# DATALOGGER_BP_V1.net
KiCad netlist of a schematic drawn in EAGLE
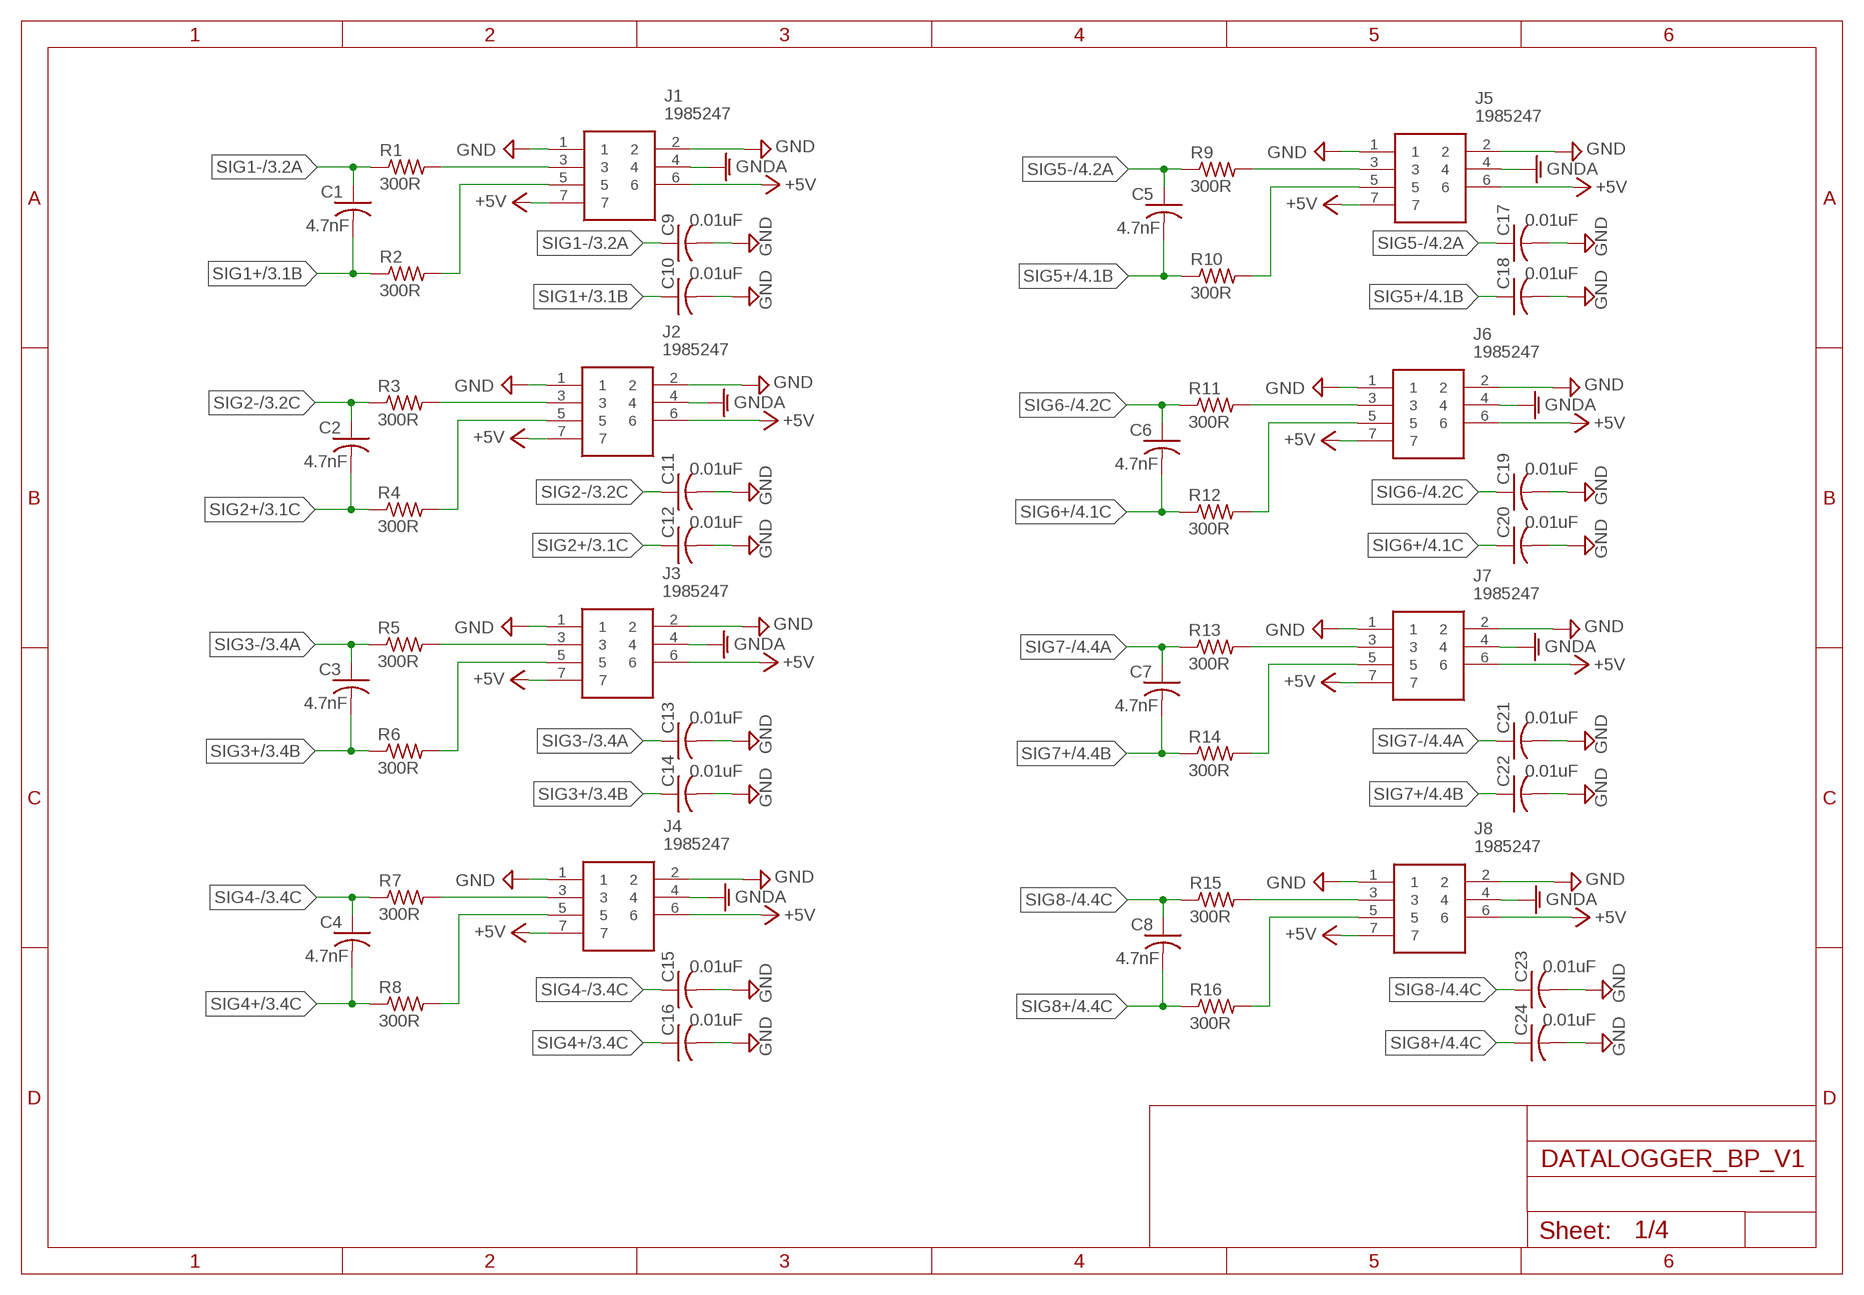
[diagram p0: schematic, sheet 1]
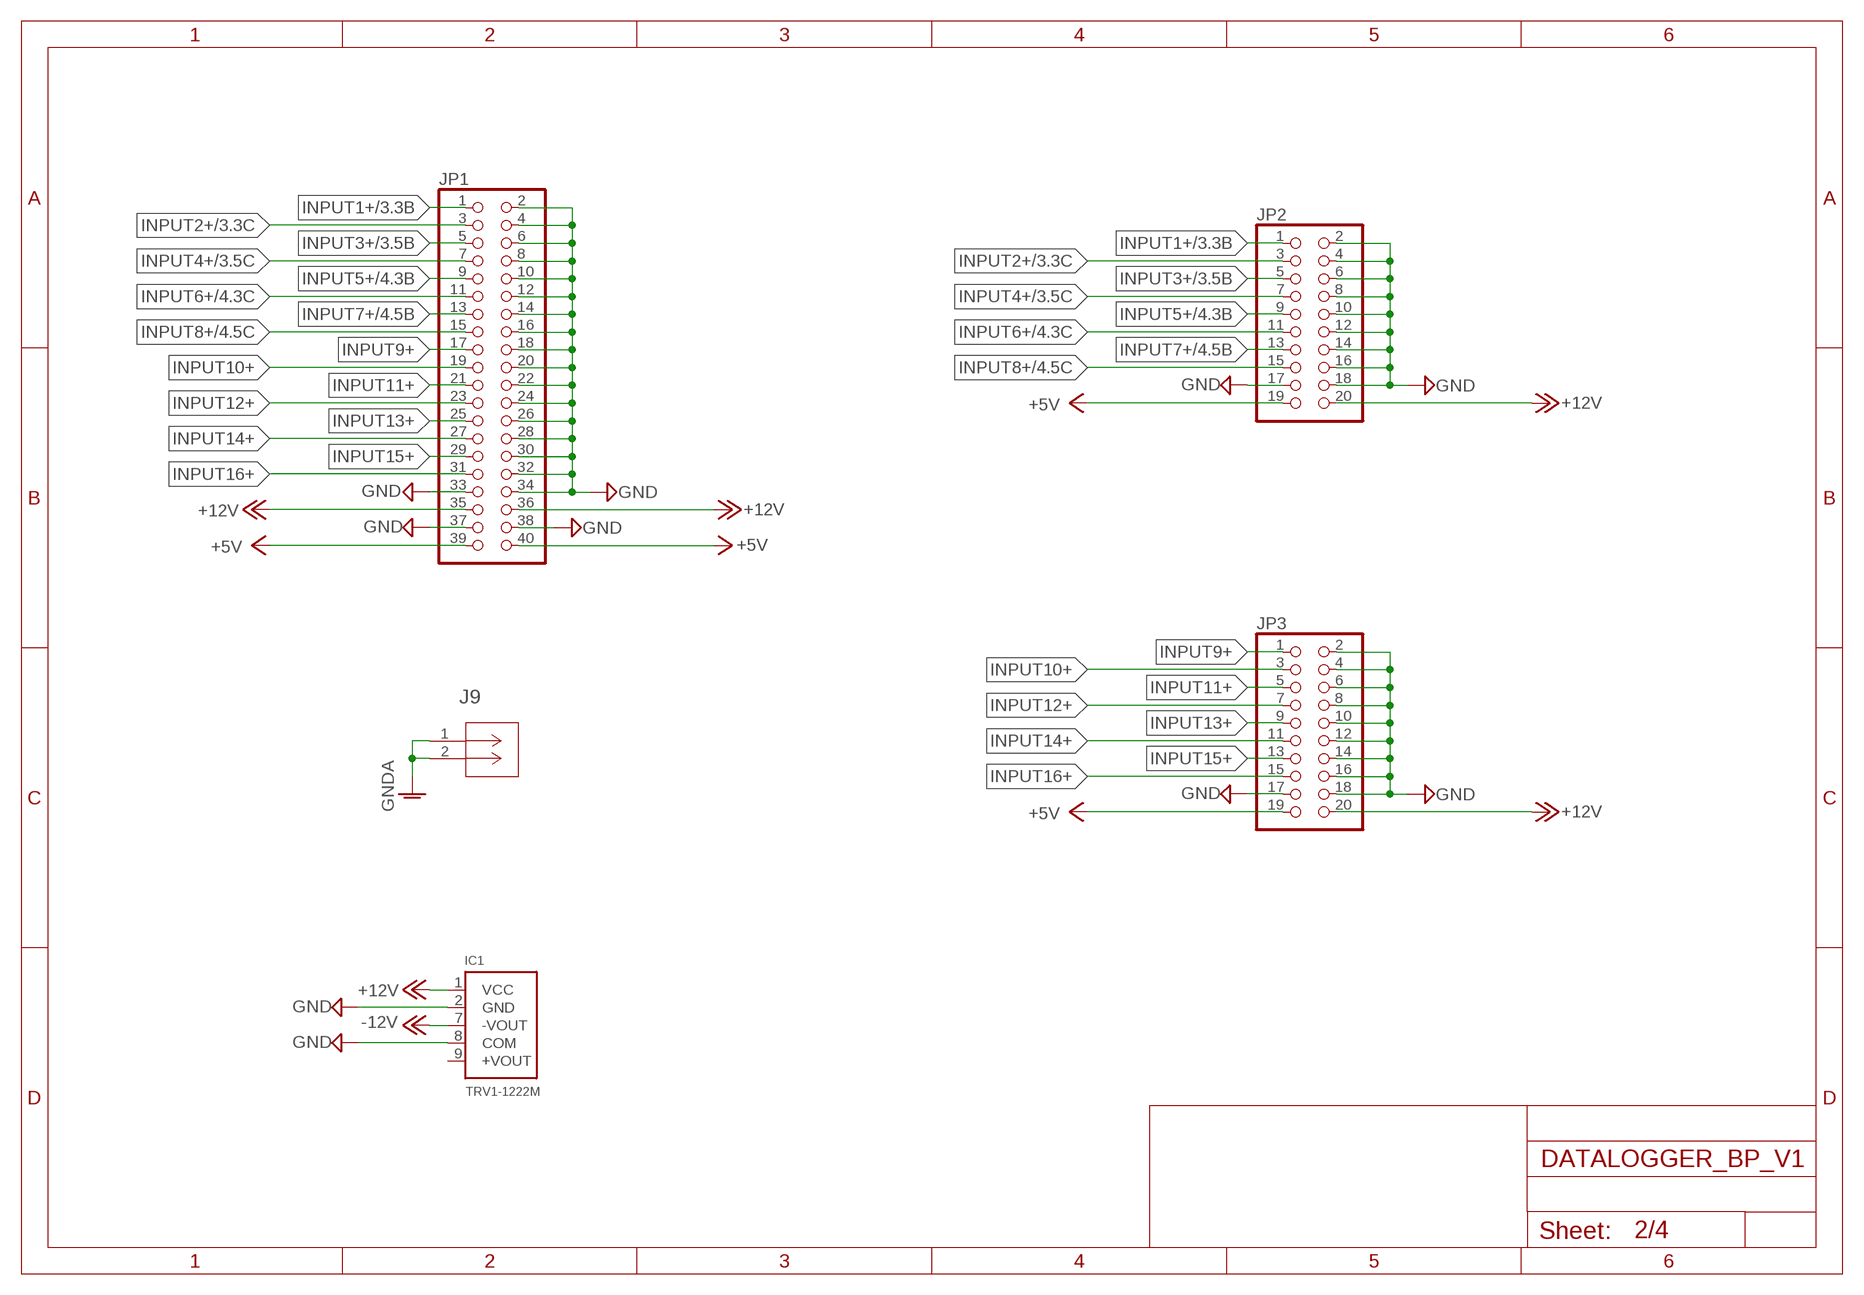
[diagram p1: schematic, sheet 2]
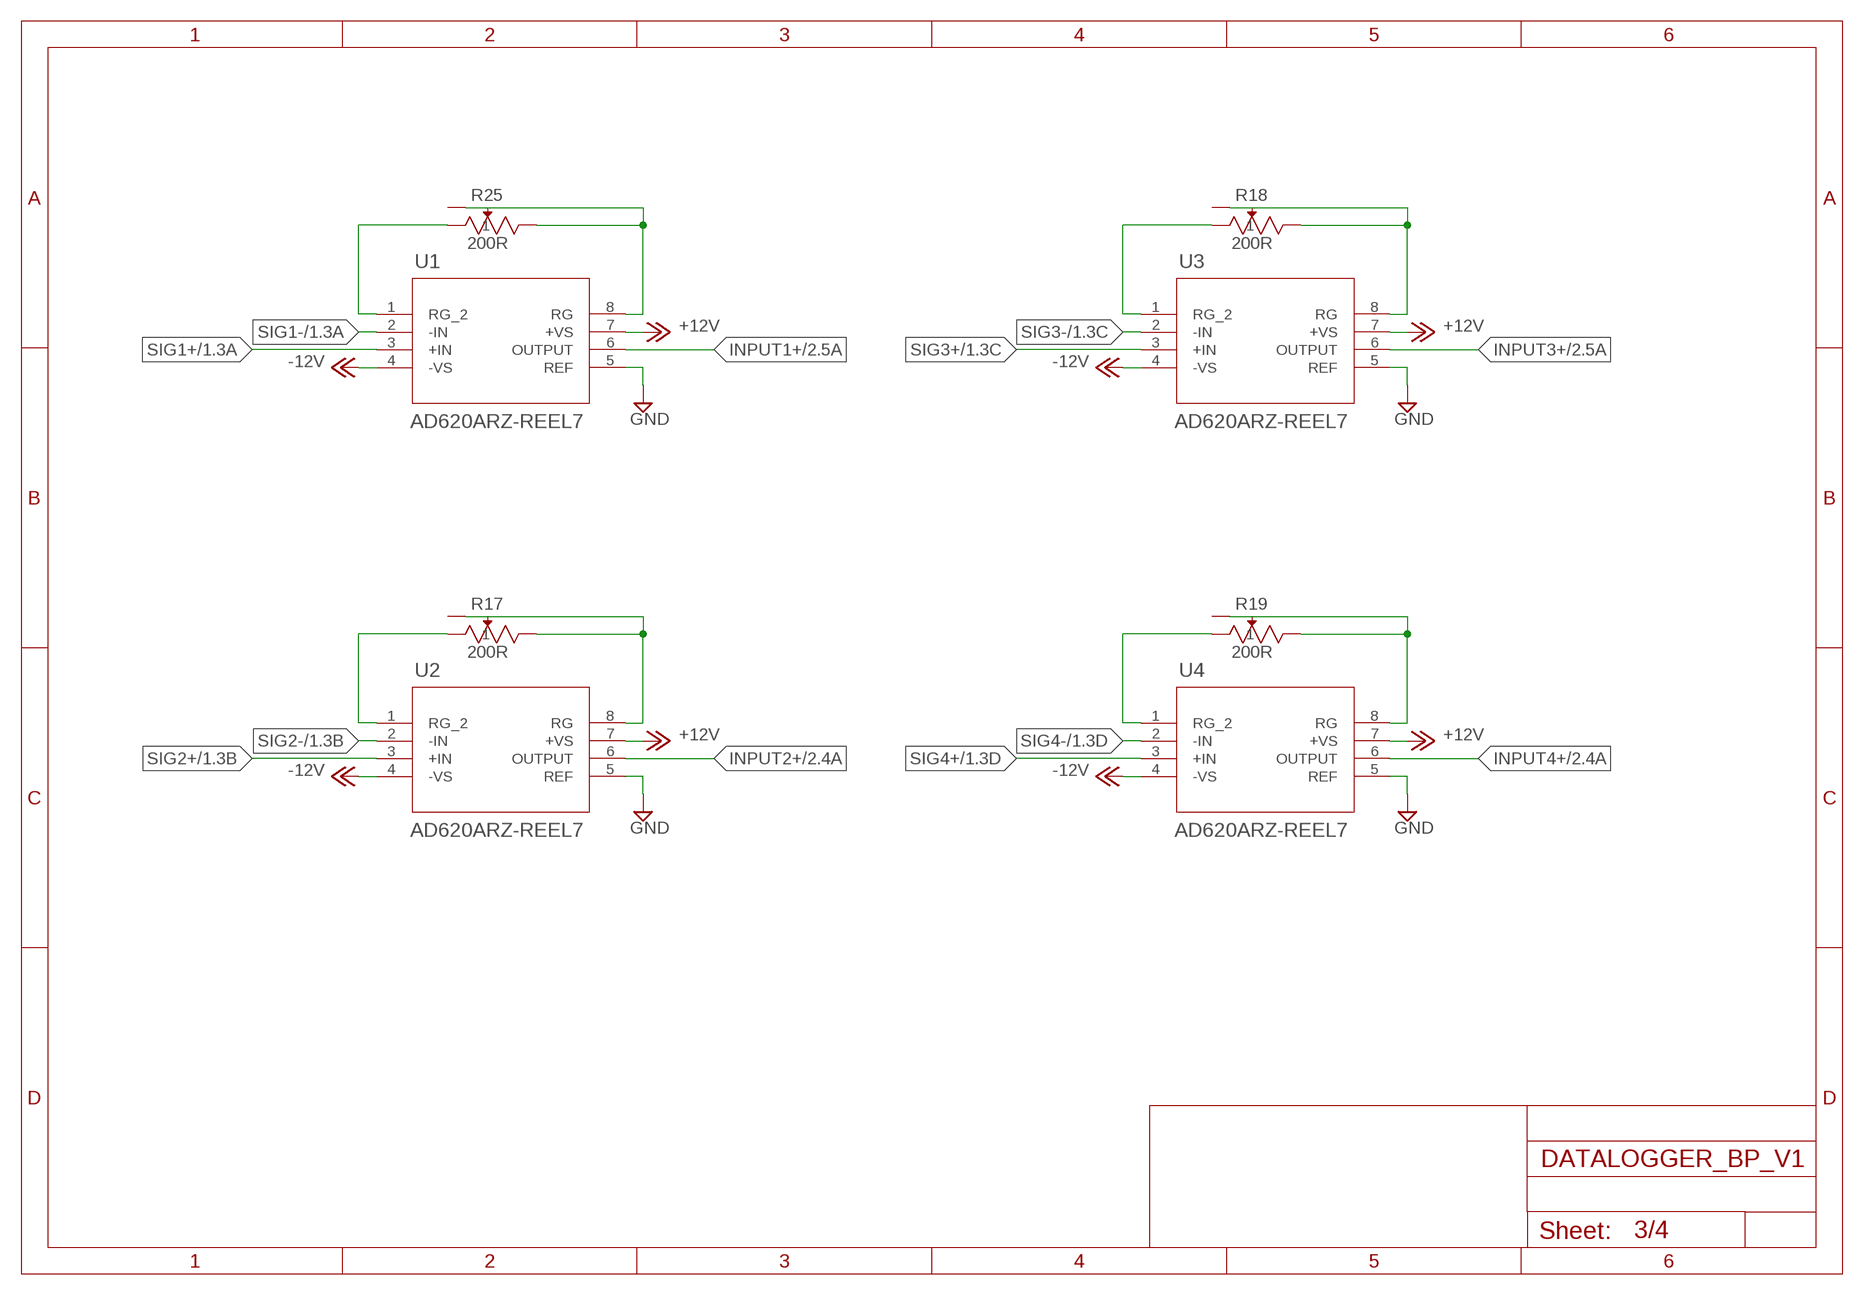
[diagram p2: schematic, sheet 3]
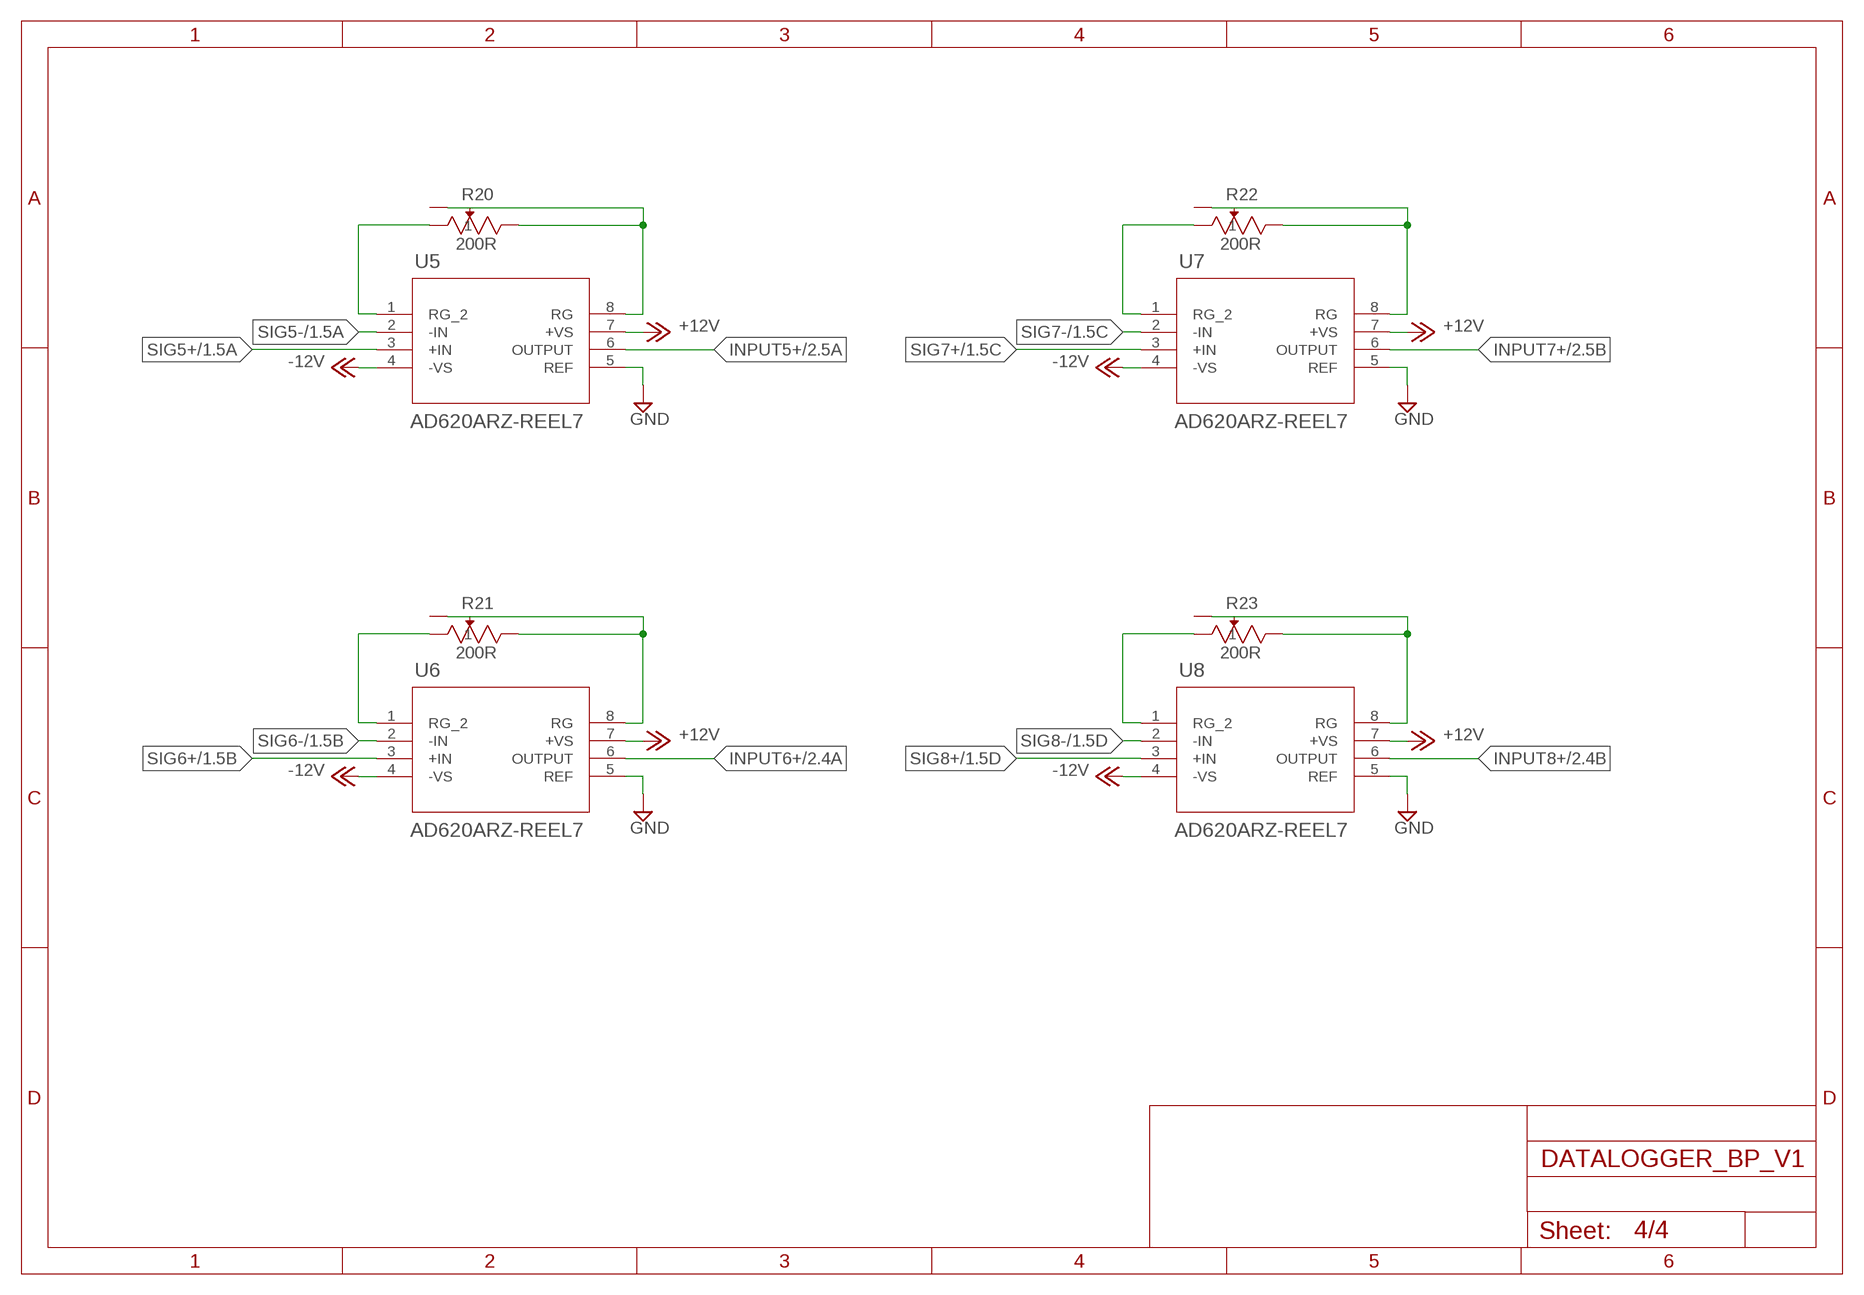
[diagram p3: schematic, sheet 4]

(export (version "E")
  (design (tool "Eeschema 10.0.6"))
  (components
    (comp (ref "R20")
      (value "200R")
      (footprint "eagle-import:RES3_22A_TTE")
      (fields (field (name "MANUFACTURER_PART_NUMBER") "22AR200LFTR"))
      (libsource (lib "eagle-import") (part "22AR200LFTR"))
    )
    (comp (ref "R21")
      (value "200R")
      (footprint "eagle-import:RES3_22A_TTE")
      (fields (field (name "MANUFACTURER_PART_NUMBER") "22AR200LFTR"))
      (libsource (lib "eagle-import") (part "22AR200LFTR"))
    )
    (comp (ref "R22")
      (value "200R")
      (footprint "eagle-import:RES3_22A_TTE")
      (fields (field (name "MANUFACTURER_PART_NUMBER") "22AR200LFTR"))
      (libsource (lib "eagle-import") (part "22AR200LFTR"))
    )
    (comp (ref "R23")
      (value "200R")
      (footprint "eagle-import:RES3_22A_TTE")
      (fields (field (name "MANUFACTURER_PART_NUMBER") "22AR200LFTR"))
      (libsource (lib "eagle-import") (part "22AR200LFTR"))
    )
    (comp (ref "U5")
      (value "AD620ARZ-REEL7")
      (footprint "eagle-import:R_8_ADI")
      (libsource (lib "eagle-import") (part "AD620ARZ-REEL7"))
    )
    (comp (ref "U6")
      (value "AD620ARZ-REEL7")
      (footprint "eagle-import:R_8_ADI")
      (libsource (lib "eagle-import") (part "AD620ARZ-REEL7"))
    )
    (comp (ref "U7")
      (value "AD620ARZ-REEL7")
      (footprint "eagle-import:R_8_ADI")
      (libsource (lib "eagle-import") (part "AD620ARZ-REEL7"))
    )
    (comp (ref "U8")
      (value "AD620ARZ-REEL7")
      (footprint "eagle-import:R_8_ADI")
      (libsource (lib "eagle-import") (part "AD620ARZ-REEL7"))
    )
    (comp (ref "R17")
      (value "200R")
      (footprint "eagle-import:RES3_22A_TTE")
      (fields (field (name "MANUFACTURER_PART_NUMBER") "22AR200LFTR"))
      (libsource (lib "eagle-import") (part "22AR200LFTR"))
    )
    (comp (ref "R18")
      (value "200R")
      (footprint "eagle-import:RES3_22A_TTE")
      (fields (field (name "MANUFACTURER_PART_NUMBER") "22AR200LFTR"))
      (libsource (lib "eagle-import") (part "22AR200LFTR"))
    )
    (comp (ref "R19")
      (value "200R")
      (footprint "eagle-import:RES3_22A_TTE")
      (fields (field (name "MANUFACTURER_PART_NUMBER") "22AR200LFTR"))
      (libsource (lib "eagle-import") (part "22AR200LFTR"))
    )
    (comp (ref "R25")
      (value "200R")
      (footprint "eagle-import:RES3_22A_TTE")
      (fields (field (name "MANUFACTURER_PART_NUMBER") "22AR200LFTR"))
      (libsource (lib "eagle-import") (part "22AR200LFTR"))
    )
    (comp (ref "U1")
      (value "AD620ARZ-REEL7")
      (footprint "eagle-import:R_8_ADI")
      (libsource (lib "eagle-import") (part "AD620ARZ-REEL7"))
    )
    (comp (ref "U2")
      (value "AD620ARZ-REEL7")
      (footprint "eagle-import:R_8_ADI")
      (libsource (lib "eagle-import") (part "AD620ARZ-REEL7"))
    )
    (comp (ref "U3")
      (value "AD620ARZ-REEL7")
      (footprint "eagle-import:R_8_ADI")
      (libsource (lib "eagle-import") (part "AD620ARZ-REEL7"))
    )
    (comp (ref "U4")
      (value "AD620ARZ-REEL7")
      (footprint "eagle-import:R_8_ADI")
      (libsource (lib "eagle-import") (part "AD620ARZ-REEL7"))
    )
    (comp (ref "C1")
      (value "4.7nF")
      (footprint "eagle-import:C0805")
      (libsource (lib "eagle-import") (part "C-USC0805"))
    )
    (comp (ref "C2")
      (value "4.7nF")
      (footprint "eagle-import:C0805")
      (libsource (lib "eagle-import") (part "C-USC0805"))
    )
    (comp (ref "C3")
      (value "4.7nF")
      (footprint "eagle-import:C0805")
      (libsource (lib "eagle-import") (part "C-USC0805"))
    )
    (comp (ref "C4")
      (value "4.7nF")
      (footprint "eagle-import:C0805")
      (libsource (lib "eagle-import") (part "C-USC0805"))
    )
    (comp (ref "C5")
      (value "4.7nF")
      (footprint "eagle-import:C0805")
      (libsource (lib "eagle-import") (part "C-USC0805"))
    )
    (comp (ref "C6")
      (value "4.7nF")
      (footprint "eagle-import:C0805")
      (libsource (lib "eagle-import") (part "C-USC0805"))
    )
    (comp (ref "C7")
      (value "4.7nF")
      (footprint "eagle-import:C0805")
      (libsource (lib "eagle-import") (part "C-USC0805"))
    )
    (comp (ref "C8")
      (value "4.7nF")
      (footprint "eagle-import:C0805")
      (libsource (lib "eagle-import") (part "C-USC0805"))
    )
    (comp (ref "C9")
      (value "0.01uF")
      (footprint "eagle-import:C0805")
      (libsource (lib "eagle-import") (part "C-USC0805"))
    )
    (comp (ref "C10")
      (value "0.01uF")
      (footprint "eagle-import:C0805")
      (libsource (lib "eagle-import") (part "C-USC0805"))
    )
    (comp (ref "C11")
      (value "0.01uF")
      (footprint "eagle-import:C0805")
      (libsource (lib "eagle-import") (part "C-USC0805"))
    )
    (comp (ref "C12")
      (value "0.01uF")
      (footprint "eagle-import:C0805")
      (libsource (lib "eagle-import") (part "C-USC0805"))
    )
    (comp (ref "C13")
      (value "0.01uF")
      (footprint "eagle-import:C0805")
      (libsource (lib "eagle-import") (part "C-USC0805"))
    )
    (comp (ref "C14")
      (value "0.01uF")
      (footprint "eagle-import:C0805")
      (libsource (lib "eagle-import") (part "C-USC0805"))
    )
    (comp (ref "C15")
      (value "0.01uF")
      (footprint "eagle-import:C0805")
      (libsource (lib "eagle-import") (part "C-USC0805"))
    )
    (comp (ref "C16")
      (value "0.01uF")
      (footprint "eagle-import:C0805")
      (libsource (lib "eagle-import") (part "C-USC0805"))
    )
    (comp (ref "C17")
      (value "0.01uF")
      (footprint "eagle-import:C0805")
      (libsource (lib "eagle-import") (part "C-USC0805"))
    )
    (comp (ref "C18")
      (value "0.01uF")
      (footprint "eagle-import:C0805")
      (libsource (lib "eagle-import") (part "C-USC0805"))
    )
    (comp (ref "C19")
      (value "0.01uF")
      (footprint "eagle-import:C0805")
      (libsource (lib "eagle-import") (part "C-USC0805"))
    )
    (comp (ref "C20")
      (value "0.01uF")
      (footprint "eagle-import:C0805")
      (libsource (lib "eagle-import") (part "C-USC0805"))
    )
    (comp (ref "C21")
      (value "0.01uF")
      (footprint "eagle-import:C0805")
      (libsource (lib "eagle-import") (part "C-USC0805"))
    )
    (comp (ref "C22")
      (value "0.01uF")
      (footprint "eagle-import:C0805")
      (libsource (lib "eagle-import") (part "C-USC0805"))
    )
    (comp (ref "C23")
      (value "0.01uF")
      (footprint "eagle-import:C0805")
      (libsource (lib "eagle-import") (part "C-USC0805"))
    )
    (comp (ref "C24")
      (value "0.01uF")
      (footprint "eagle-import:C0805")
      (libsource (lib "eagle-import") (part "C-USC0805"))
    )
    (comp (ref "J1")
      (value "1985247")
      (footprint "eagle-import:1985247")
      (fields (field (name "MOUSER_PART_NUMBER") "651-1985247"))
      (libsource (lib "eagle-import") (part "1985247"))
    )
    (comp (ref "J2")
      (value "1985247")
      (footprint "eagle-import:1985247")
      (fields (field (name "MOUSER_PART_NUMBER") "651-1985247"))
      (libsource (lib "eagle-import") (part "1985247"))
    )
    (comp (ref "J3")
      (value "1985247")
      (footprint "eagle-import:1985247")
      (fields (field (name "MOUSER_PART_NUMBER") "651-1985247"))
      (libsource (lib "eagle-import") (part "1985247"))
    )
    (comp (ref "J4")
      (value "1985247")
      (footprint "eagle-import:1985247")
      (fields (field (name "MOUSER_PART_NUMBER") "651-1985247"))
      (libsource (lib "eagle-import") (part "1985247"))
    )
    (comp (ref "J5")
      (value "1985247")
      (footprint "eagle-import:1985247")
      (fields (field (name "MOUSER_PART_NUMBER") "651-1985247"))
      (libsource (lib "eagle-import") (part "1985247"))
    )
    (comp (ref "J6")
      (value "1985247")
      (footprint "eagle-import:1985247")
      (fields (field (name "MOUSER_PART_NUMBER") "651-1985247"))
      (libsource (lib "eagle-import") (part "1985247"))
    )
    (comp (ref "J7")
      (value "1985247")
      (footprint "eagle-import:1985247")
      (fields (field (name "MOUSER_PART_NUMBER") "651-1985247"))
      (libsource (lib "eagle-import") (part "1985247"))
    )
    (comp (ref "J8")
      (value "1985247")
      (footprint "eagle-import:1985247")
      (fields (field (name "MOUSER_PART_NUMBER") "651-1985247"))
      (libsource (lib "eagle-import") (part "1985247"))
    )
    (comp (ref "R1")
      (value "300R")
      (footprint "eagle-import:R0805")
      (libsource (lib "eagle-import") (part "R-US_R0805"))
    )
    (comp (ref "R2")
      (value "300R")
      (footprint "eagle-import:R0805")
      (libsource (lib "eagle-import") (part "R-US_R0805"))
    )
    (comp (ref "R3")
      (value "300R")
      (footprint "eagle-import:R0805")
      (libsource (lib "eagle-import") (part "R-US_R0805"))
    )
    (comp (ref "R4")
      (value "300R")
      (footprint "eagle-import:R0805")
      (libsource (lib "eagle-import") (part "R-US_R0805"))
    )
    (comp (ref "R5")
      (value "300R")
      (footprint "eagle-import:R0805")
      (libsource (lib "eagle-import") (part "R-US_R0805"))
    )
    (comp (ref "R6")
      (value "300R")
      (footprint "eagle-import:R0805")
      (libsource (lib "eagle-import") (part "R-US_R0805"))
    )
    (comp (ref "R7")
      (value "300R")
      (footprint "eagle-import:R0805")
      (libsource (lib "eagle-import") (part "R-US_R0805"))
    )
    (comp (ref "R8")
      (value "300R")
      (footprint "eagle-import:R0805")
      (libsource (lib "eagle-import") (part "R-US_R0805"))
    )
    (comp (ref "R9")
      (value "300R")
      (footprint "eagle-import:R0805")
      (libsource (lib "eagle-import") (part "R-US_R0805"))
    )
    (comp (ref "R10")
      (value "300R")
      (footprint "eagle-import:R0805")
      (libsource (lib "eagle-import") (part "R-US_R0805"))
    )
    (comp (ref "R11")
      (value "300R")
      (footprint "eagle-import:R0805")
      (libsource (lib "eagle-import") (part "R-US_R0805"))
    )
    (comp (ref "R12")
      (value "300R")
      (footprint "eagle-import:R0805")
      (libsource (lib "eagle-import") (part "R-US_R0805"))
    )
    (comp (ref "R13")
      (value "300R")
      (footprint "eagle-import:R0805")
      (libsource (lib "eagle-import") (part "R-US_R0805"))
    )
    (comp (ref "R14")
      (value "300R")
      (footprint "eagle-import:R0805")
      (libsource (lib "eagle-import") (part "R-US_R0805"))
    )
    (comp (ref "R15")
      (value "300R")
      (footprint "eagle-import:R0805")
      (libsource (lib "eagle-import") (part "R-US_R0805"))
    )
    (comp (ref "R16")
      (value "300R")
      (footprint "eagle-import:R0805")
      (libsource (lib "eagle-import") (part "R-US_R0805"))
    )
    (comp (ref "IC1")
      (value "TRV1-1222M")
      (footprint "eagle-import:TRV1-1222M")
      (libsource (lib "eagle-import") (part "TRV1-1222M"))
    )
    (comp (ref "J9")
      (value "1755736")
      (footprint "eagle-import:CONN_1924305")
      (libsource (lib "eagle-import") (part "1755736"))
    )
    (comp (ref "JP1")
      (value "PINHD-2X20")
      (footprint "eagle-import:2X20")
      (libsource (lib "eagle-import") (part "PINHD-2X20"))
    )
    (comp (ref "JP2")
      (value "PINHD-2X10")
      (footprint "eagle-import:2X10")
      (libsource (lib "eagle-import") (part "PINHD-2X10"))
    )
    (comp (ref "JP3")
      (value "PINHD-2X10")
      (footprint "eagle-import:2X10")
      (libsource (lib "eagle-import") (part "PINHD-2X10"))
    )
  )
  (nets
    (net (code "1") (name "+5V") (class "Default")
      (node (ref "J1") (pin "6") (pinfunction "6_6") (pintype "bidirectional"))
      (node (ref "J1") (pin "7") (pinfunction "7_7") (pintype "bidirectional"))
      (node (ref "J2") (pin "6") (pinfunction "6_6") (pintype "bidirectional"))
      (node (ref "J2") (pin "7") (pinfunction "7_7") (pintype "bidirectional"))
      (node (ref "J3") (pin "6") (pinfunction "6_6") (pintype "bidirectional"))
      (node (ref "J3") (pin "7") (pinfunction "7_7") (pintype "bidirectional"))
      (node (ref "J4") (pin "6") (pinfunction "6_6") (pintype "bidirectional"))
      (node (ref "J4") (pin "7") (pinfunction "7_7") (pintype "bidirectional"))
      (node (ref "J5") (pin "6") (pinfunction "6_6") (pintype "bidirectional"))
      (node (ref "J5") (pin "7") (pinfunction "7_7") (pintype "bidirectional"))
      (node (ref "J6") (pin "6") (pinfunction "6_6") (pintype "bidirectional"))
      (node (ref "J6") (pin "7") (pinfunction "7_7") (pintype "bidirectional"))
      (node (ref "J7") (pin "6") (pinfunction "6_6") (pintype "bidirectional"))
      (node (ref "J7") (pin "7") (pinfunction "7_7") (pintype "bidirectional"))
      (node (ref "J8") (pin "6") (pinfunction "6_6") (pintype "bidirectional"))
      (node (ref "J8") (pin "7") (pinfunction "7_7") (pintype "bidirectional"))
      (node (ref "JP1") (pin "39") (pinfunction "39_39") (pintype "passive"))
      (node (ref "JP1") (pin "40") (pinfunction "40_40") (pintype "passive"))
      (node (ref "JP2") (pin "19") (pinfunction "19_19") (pintype "passive"))
      (node (ref "JP3") (pin "19") (pinfunction "19_19") (pintype "passive"))
    )
    (net (code "2") (name "+12V") (class "Default")
      (node (ref "IC1") (pin "1") (pinfunction "VCC_1") (pintype "bidirectional"))
      (node (ref "JP1") (pin "35") (pinfunction "35_35") (pintype "passive"))
      (node (ref "JP1") (pin "36") (pinfunction "36_36") (pintype "passive"))
      (node (ref "JP2") (pin "20") (pinfunction "20_20") (pintype "passive"))
      (node (ref "JP3") (pin "20") (pinfunction "20_20") (pintype "passive"))
      (node (ref "U1") (pin "7") (pinfunction "+VS_7") (pintype "power_in"))
      (node (ref "U2") (pin "7") (pinfunction "+VS_7") (pintype "power_in"))
      (node (ref "U3") (pin "7") (pinfunction "+VS_7") (pintype "power_in"))
      (node (ref "U4") (pin "7") (pinfunction "+VS_7") (pintype "power_in"))
      (node (ref "U5") (pin "7") (pinfunction "+VS_7") (pintype "power_in"))
      (node (ref "U6") (pin "7") (pinfunction "+VS_7") (pintype "power_in"))
      (node (ref "U7") (pin "7") (pinfunction "+VS_7") (pintype "power_in"))
      (node (ref "U8") (pin "7") (pinfunction "+VS_7") (pintype "power_in"))
    )
    (net (code "3") (name "-12V") (class "Default")
      (node (ref "IC1") (pin "7") (pinfunction "-VOUT_7") (pintype "bidirectional"))
      (node (ref "U1") (pin "4") (pinfunction "-VS_4") (pintype "power_in"))
      (node (ref "U2") (pin "4") (pinfunction "-VS_4") (pintype "power_in"))
      (node (ref "U3") (pin "4") (pinfunction "-VS_4") (pintype "power_in"))
      (node (ref "U4") (pin "4") (pinfunction "-VS_4") (pintype "power_in"))
      (node (ref "U5") (pin "4") (pinfunction "-VS_4") (pintype "power_in"))
      (node (ref "U6") (pin "4") (pinfunction "-VS_4") (pintype "power_in"))
      (node (ref "U7") (pin "4") (pinfunction "-VS_4") (pintype "power_in"))
      (node (ref "U8") (pin "4") (pinfunction "-VS_4") (pintype "power_in"))
    )
    (net (code "4") (name "GND") (class "Default")
      (node (ref "C10") (pin "2") (pinfunction "2_2") (pintype "passive"))
      (node (ref "C11") (pin "2") (pinfunction "2_2") (pintype "passive"))
      (node (ref "C12") (pin "2") (pinfunction "2_2") (pintype "passive"))
      (node (ref "C13") (pin "2") (pinfunction "2_2") (pintype "passive"))
      (node (ref "C14") (pin "2") (pinfunction "2_2") (pintype "passive"))
      (node (ref "C15") (pin "2") (pinfunction "2_2") (pintype "passive"))
      (node (ref "C16") (pin "2") (pinfunction "2_2") (pintype "passive"))
      (node (ref "C17") (pin "2") (pinfunction "2_2") (pintype "passive"))
      (node (ref "C18") (pin "2") (pinfunction "2_2") (pintype "passive"))
      (node (ref "C19") (pin "2") (pinfunction "2_2") (pintype "passive"))
      (node (ref "C20") (pin "2") (pinfunction "2_2") (pintype "passive"))
      (node (ref "C21") (pin "2") (pinfunction "2_2") (pintype "passive"))
      (node (ref "C22") (pin "2") (pinfunction "2_2") (pintype "passive"))
      (node (ref "C23") (pin "2") (pinfunction "2_2") (pintype "passive"))
      (node (ref "C24") (pin "2") (pinfunction "2_2") (pintype "passive"))
      (node (ref "C9") (pin "2") (pinfunction "2_2") (pintype "passive"))
      (node (ref "IC1") (pin "2") (pinfunction "GND_2") (pintype "bidirectional"))
      (node (ref "IC1") (pin "8") (pinfunction "COM_8") (pintype "bidirectional"))
      (node (ref "J1") (pin "1") (pinfunction "1_1") (pintype "bidirectional"))
      (node (ref "J1") (pin "2") (pinfunction "2_2") (pintype "bidirectional"))
      (node (ref "J2") (pin "1") (pinfunction "1_1") (pintype "bidirectional"))
      (node (ref "J2") (pin "2") (pinfunction "2_2") (pintype "bidirectional"))
      (node (ref "J3") (pin "1") (pinfunction "1_1") (pintype "bidirectional"))
      (node (ref "J3") (pin "2") (pinfunction "2_2") (pintype "bidirectional"))
      (node (ref "J4") (pin "1") (pinfunction "1_1") (pintype "bidirectional"))
      (node (ref "J4") (pin "2") (pinfunction "2_2") (pintype "bidirectional"))
      (node (ref "J5") (pin "1") (pinfunction "1_1") (pintype "bidirectional"))
      (node (ref "J5") (pin "2") (pinfunction "2_2") (pintype "bidirectional"))
      (node (ref "J6") (pin "1") (pinfunction "1_1") (pintype "bidirectional"))
      (node (ref "J6") (pin "2") (pinfunction "2_2") (pintype "bidirectional"))
      (node (ref "J7") (pin "1") (pinfunction "1_1") (pintype "bidirectional"))
      (node (ref "J7") (pin "2") (pinfunction "2_2") (pintype "bidirectional"))
      (node (ref "J8") (pin "1") (pinfunction "1_1") (pintype "bidirectional"))
      (node (ref "J8") (pin "2") (pinfunction "2_2") (pintype "bidirectional"))
      (node (ref "JP1") (pin "10") (pinfunction "10_10") (pintype "passive"))
      (node (ref "JP1") (pin "12") (pinfunction "12_12") (pintype "passive"))
      (node (ref "JP1") (pin "14") (pinfunction "14_14") (pintype "passive"))
      (node (ref "JP1") (pin "16") (pinfunction "16_16") (pintype "passive"))
      (node (ref "JP1") (pin "18") (pinfunction "18_18") (pintype "passive"))
      (node (ref "JP1") (pin "2") (pinfunction "2_2") (pintype "passive"))
      (node (ref "JP1") (pin "20") (pinfunction "20_20") (pintype "passive"))
      (node (ref "JP1") (pin "22") (pinfunction "22_22") (pintype "passive"))
      (node (ref "JP1") (pin "24") (pinfunction "24_24") (pintype "passive"))
      (node (ref "JP1") (pin "26") (pinfunction "26_26") (pintype "passive"))
      (node (ref "JP1") (pin "28") (pinfunction "28_28") (pintype "passive"))
      (node (ref "JP1") (pin "30") (pinfunction "30_30") (pintype "passive"))
      (node (ref "JP1") (pin "32") (pinfunction "32_32") (pintype "passive"))
      (node (ref "JP1") (pin "33") (pinfunction "33_33") (pintype "passive"))
      (node (ref "JP1") (pin "34") (pinfunction "34_34") (pintype "passive"))
      (node (ref "JP1") (pin "37") (pinfunction "37_37") (pintype "passive"))
      (node (ref "JP1") (pin "38") (pinfunction "38_38") (pintype "passive"))
      (node (ref "JP1") (pin "4") (pinfunction "4_4") (pintype "passive"))
      (node (ref "JP1") (pin "6") (pinfunction "6_6") (pintype "passive"))
      (node (ref "JP1") (pin "8") (pinfunction "8_8") (pintype "passive"))
      (node (ref "JP2") (pin "10") (pinfunction "10_10") (pintype "passive"))
      (node (ref "JP2") (pin "12") (pinfunction "12_12") (pintype "passive"))
      (node (ref "JP2") (pin "14") (pinfunction "14_14") (pintype "passive"))
      (node (ref "JP2") (pin "16") (pinfunction "16_16") (pintype "passive"))
      (node (ref "JP2") (pin "17") (pinfunction "17_17") (pintype "passive"))
      (node (ref "JP2") (pin "18") (pinfunction "18_18") (pintype "passive"))
      (node (ref "JP2") (pin "2") (pinfunction "2_2") (pintype "passive"))
      (node (ref "JP2") (pin "4") (pinfunction "4_4") (pintype "passive"))
      (node (ref "JP2") (pin "6") (pinfunction "6_6") (pintype "passive"))
      (node (ref "JP2") (pin "8") (pinfunction "8_8") (pintype "passive"))
      (node (ref "JP3") (pin "10") (pinfunction "10_10") (pintype "passive"))
      (node (ref "JP3") (pin "12") (pinfunction "12_12") (pintype "passive"))
      (node (ref "JP3") (pin "14") (pinfunction "14_14") (pintype "passive"))
      (node (ref "JP3") (pin "16") (pinfunction "16_16") (pintype "passive"))
      (node (ref "JP3") (pin "17") (pinfunction "17_17") (pintype "passive"))
      (node (ref "JP3") (pin "18") (pinfunction "18_18") (pintype "passive"))
      (node (ref "JP3") (pin "2") (pinfunction "2_2") (pintype "passive"))
      (node (ref "JP3") (pin "4") (pinfunction "4_4") (pintype "passive"))
      (node (ref "JP3") (pin "6") (pinfunction "6_6") (pintype "passive"))
      (node (ref "JP3") (pin "8") (pinfunction "8_8") (pintype "passive"))
      (node (ref "U1") (pin "5") (pinfunction "REF_5") (pintype "passive"))
      (node (ref "U2") (pin "5") (pinfunction "REF_5") (pintype "passive"))
      (node (ref "U3") (pin "5") (pinfunction "REF_5") (pintype "passive"))
      (node (ref "U4") (pin "5") (pinfunction "REF_5") (pintype "passive"))
      (node (ref "U5") (pin "5") (pinfunction "REF_5") (pintype "passive"))
      (node (ref "U6") (pin "5") (pinfunction "REF_5") (pintype "passive"))
      (node (ref "U7") (pin "5") (pinfunction "REF_5") (pintype "passive"))
      (node (ref "U8") (pin "5") (pinfunction "REF_5") (pintype "passive"))
    )
    (net (code "5") (name "GNDA") (class "Default")
      (node (ref "J1") (pin "4") (pinfunction "4_4") (pintype "bidirectional"))
      (node (ref "J2") (pin "4") (pinfunction "4_4") (pintype "bidirectional"))
      (node (ref "J3") (pin "4") (pinfunction "4_4") (pintype "bidirectional"))
      (node (ref "J4") (pin "4") (pinfunction "4_4") (pintype "bidirectional"))
      (node (ref "J5") (pin "4") (pinfunction "4_4") (pintype "bidirectional"))
      (node (ref "J6") (pin "4") (pinfunction "4_4") (pintype "bidirectional"))
      (node (ref "J7") (pin "4") (pinfunction "4_4") (pintype "bidirectional"))
      (node (ref "J8") (pin "4") (pinfunction "4_4") (pintype "bidirectional"))
      (node (ref "J9") (pin "1") (pinfunction "1_1") (pintype "passive"))
      (node (ref "J9") (pin "2") (pinfunction "2_2") (pintype "passive"))
    )
    (net (code "6") (name "INPUT1+") (class "Default")
      (node (ref "JP1") (pin "1") (pinfunction "1_1") (pintype "passive"))
      (node (ref "JP2") (pin "1") (pinfunction "1_1") (pintype "passive"))
      (node (ref "U1") (pin "6") (pinfunction "OUTPUT_6") (pintype "passive"))
    )
    (net (code "7") (name "INPUT2+") (class "Default")
      (node (ref "JP1") (pin "3") (pinfunction "3_3") (pintype "passive"))
      (node (ref "JP2") (pin "3") (pinfunction "3_3") (pintype "passive"))
      (node (ref "U2") (pin "6") (pinfunction "OUTPUT_6") (pintype "passive"))
    )
    (net (code "8") (name "INPUT3+") (class "Default")
      (node (ref "JP1") (pin "5") (pinfunction "5_5") (pintype "passive"))
      (node (ref "JP2") (pin "5") (pinfunction "5_5") (pintype "passive"))
      (node (ref "U3") (pin "6") (pinfunction "OUTPUT_6") (pintype "passive"))
    )
    (net (code "9") (name "INPUT4+") (class "Default")
      (node (ref "JP1") (pin "7") (pinfunction "7_7") (pintype "passive"))
      (node (ref "JP2") (pin "7") (pinfunction "7_7") (pintype "passive"))
      (node (ref "U4") (pin "6") (pinfunction "OUTPUT_6") (pintype "passive"))
    )
    (net (code "10") (name "INPUT5+") (class "Default")
      (node (ref "JP1") (pin "9") (pinfunction "9_9") (pintype "passive"))
      (node (ref "JP2") (pin "9") (pinfunction "9_9") (pintype "passive"))
      (node (ref "U5") (pin "6") (pinfunction "OUTPUT_6") (pintype "passive"))
    )
    (net (code "11") (name "INPUT6+") (class "Default")
      (node (ref "JP1") (pin "11") (pinfunction "11_11") (pintype "passive"))
      (node (ref "JP2") (pin "11") (pinfunction "11_11") (pintype "passive"))
      (node (ref "U6") (pin "6") (pinfunction "OUTPUT_6") (pintype "passive"))
    )
    (net (code "12") (name "INPUT7+") (class "Default")
      (node (ref "JP1") (pin "13") (pinfunction "13_13") (pintype "passive"))
      (node (ref "JP2") (pin "13") (pinfunction "13_13") (pintype "passive"))
      (node (ref "U7") (pin "6") (pinfunction "OUTPUT_6") (pintype "passive"))
    )
    (net (code "13") (name "INPUT8+") (class "Default")
      (node (ref "JP1") (pin "15") (pinfunction "15_15") (pintype "passive"))
      (node (ref "JP2") (pin "15") (pinfunction "15_15") (pintype "passive"))
      (node (ref "U8") (pin "6") (pinfunction "OUTPUT_6") (pintype "passive"))
    )
    (net (code "14") (name "INPUT9+") (class "Default")
      (node (ref "JP1") (pin "17") (pinfunction "17_17") (pintype "passive"))
      (node (ref "JP3") (pin "1") (pinfunction "1_1") (pintype "passive"))
    )
    (net (code "15") (name "INPUT10+") (class "Default")
      (node (ref "JP1") (pin "19") (pinfunction "19_19") (pintype "passive"))
      (node (ref "JP3") (pin "3") (pinfunction "3_3") (pintype "passive"))
    )
    (net (code "16") (name "INPUT11+") (class "Default")
      (node (ref "JP1") (pin "21") (pinfunction "21_21") (pintype "passive"))
      (node (ref "JP3") (pin "5") (pinfunction "5_5") (pintype "passive"))
    )
    (net (code "17") (name "INPUT12+") (class "Default")
      (node (ref "JP1") (pin "23") (pinfunction "23_23") (pintype "passive"))
      (node (ref "JP3") (pin "7") (pinfunction "7_7") (pintype "passive"))
    )
    (net (code "18") (name "INPUT13+") (class "Default")
      (node (ref "JP1") (pin "25") (pinfunction "25_25") (pintype "passive"))
      (node (ref "JP3") (pin "9") (pinfunction "9_9") (pintype "passive"))
    )
    (net (code "19") (name "INPUT14+") (class "Default")
      (node (ref "JP1") (pin "27") (pinfunction "27_27") (pintype "passive"))
      (node (ref "JP3") (pin "11") (pinfunction "11_11") (pintype "passive"))
    )
    (net (code "20") (name "INPUT15+") (class "Default")
      (node (ref "JP1") (pin "29") (pinfunction "29_29") (pintype "passive"))
      (node (ref "JP3") (pin "13") (pinfunction "13_13") (pintype "passive"))
    )
    (net (code "21") (name "INPUT16+") (class "Default")
      (node (ref "JP1") (pin "31") (pinfunction "31_31") (pintype "passive"))
      (node (ref "JP3") (pin "15") (pinfunction "15_15") (pintype "passive"))
    )
    (net (code "22") (name "Net-(J1-Pad3)") (class "Default")
      (node (ref "J1") (pin "3") (pinfunction "3_3") (pintype "bidirectional"))
      (node (ref "R1") (pin "2") (pinfunction "2_2") (pintype "passive"))
    )
    (net (code "23") (name "Net-(J1-Pad5)") (class "Default")
      (node (ref "J1") (pin "5") (pinfunction "5_5") (pintype "bidirectional"))
      (node (ref "R2") (pin "2") (pinfunction "2_2") (pintype "passive"))
    )
    (net (code "24") (name "Net-(J2-Pad3)") (class "Default")
      (node (ref "J2") (pin "3") (pinfunction "3_3") (pintype "bidirectional"))
      (node (ref "R3") (pin "2") (pinfunction "2_2") (pintype "passive"))
    )
    (net (code "25") (name "Net-(J2-Pad5)") (class "Default")
      (node (ref "J2") (pin "5") (pinfunction "5_5") (pintype "bidirectional"))
      (node (ref "R4") (pin "2") (pinfunction "2_2") (pintype "passive"))
    )
    (net (code "26") (name "Net-(J3-Pad3)") (class "Default")
      (node (ref "J3") (pin "3") (pinfunction "3_3") (pintype "bidirectional"))
      (node (ref "R5") (pin "2") (pinfunction "2_2") (pintype "passive"))
    )
    (net (code "27") (name "Net-(J3-Pad5)") (class "Default")
      (node (ref "J3") (pin "5") (pinfunction "5_5") (pintype "bidirectional"))
      (node (ref "R6") (pin "2") (pinfunction "2_2") (pintype "passive"))
    )
    (net (code "28") (name "Net-(J4-Pad3)") (class "Default")
      (node (ref "J4") (pin "3") (pinfunction "3_3") (pintype "bidirectional"))
      (node (ref "R7") (pin "2") (pinfunction "2_2") (pintype "passive"))
    )
    (net (code "29") (name "Net-(J4-Pad5)") (class "Default")
      (node (ref "J4") (pin "5") (pinfunction "5_5") (pintype "bidirectional"))
      (node (ref "R8") (pin "2") (pinfunction "2_2") (pintype "passive"))
    )
    (net (code "30") (name "Net-(J5-Pad3)") (class "Default")
      (node (ref "J5") (pin "3") (pinfunction "3_3") (pintype "bidirectional"))
      (node (ref "R9") (pin "2") (pinfunction "2_2") (pintype "passive"))
    )
    (net (code "31") (name "Net-(J5-Pad5)") (class "Default")
      (node (ref "J5") (pin "5") (pinfunction "5_5") (pintype "bidirectional"))
      (node (ref "R10") (pin "2") (pinfunction "2_2") (pintype "passive"))
    )
    (net (code "32") (name "Net-(J6-Pad3)") (class "Default")
      (node (ref "J6") (pin "3") (pinfunction "3_3") (pintype "bidirectional"))
      (node (ref "R11") (pin "2") (pinfunction "2_2") (pintype "passive"))
    )
    (net (code "33") (name "Net-(J6-Pad5)") (class "Default")
      (node (ref "J6") (pin "5") (pinfunction "5_5") (pintype "bidirectional"))
      (node (ref "R12") (pin "2") (pinfunction "2_2") (pintype "passive"))
    )
    (net (code "34") (name "Net-(J7-Pad3)") (class "Default")
      (node (ref "J7") (pin "3") (pinfunction "3_3") (pintype "bidirectional"))
      (node (ref "R13") (pin "2") (pinfunction "2_2") (pintype "passive"))
    )
    (net (code "35") (name "Net-(J7-Pad5)") (class "Default")
      (node (ref "J7") (pin "5") (pinfunction "5_5") (pintype "bidirectional"))
      (node (ref "R14") (pin "2") (pinfunction "2_2") (pintype "passive"))
    )
    (net (code "36") (name "Net-(J8-Pad3)") (class "Default")
      (node (ref "J8") (pin "3") (pinfunction "3_3") (pintype "bidirectional"))
      (node (ref "R15") (pin "2") (pinfunction "2_2") (pintype "passive"))
    )
    (net (code "37") (name "Net-(J8-Pad5)") (class "Default")
      (node (ref "J8") (pin "5") (pinfunction "5_5") (pintype "bidirectional"))
      (node (ref "R16") (pin "2") (pinfunction "2_2") (pintype "passive"))
    )
    (net (code "38") (name "Net-(U1-RG)") (class "Default")
      (node (ref "R25") (pin "2") (pinfunction "2_2") (pintype "passive"))
      (node (ref "R25") (pin "3") (pinfunction "3_3") (pintype "passive"))
      (node (ref "U1") (pin "8") (pinfunction "RG_8") (pintype "passive"))
    )
    (net (code "39") (name "Net-(U1-RG_2)") (class "Default")
      (node (ref "R25") (pin "1") (pinfunction "1_1") (pintype "passive"))
      (node (ref "U1") (pin "1") (pinfunction "RG_2_1") (pintype "passive"))
    )
    (net (code "40") (name "Net-(U2-RG)") (class "Default")
      (node (ref "R17") (pin "2") (pinfunction "2_2") (pintype "passive"))
      (node (ref "R17") (pin "3") (pinfunction "3_3") (pintype "passive"))
      (node (ref "U2") (pin "8") (pinfunction "RG_8") (pintype "passive"))
    )
    (net (code "41") (name "Net-(U2-RG_2)") (class "Default")
      (node (ref "R17") (pin "1") (pinfunction "1_1") (pintype "passive"))
      (node (ref "U2") (pin "1") (pinfunction "RG_2_1") (pintype "passive"))
    )
    (net (code "42") (name "Net-(U3-RG)") (class "Default")
      (node (ref "R18") (pin "2") (pinfunction "2_2") (pintype "passive"))
      (node (ref "R18") (pin "3") (pinfunction "3_3") (pintype "passive"))
      (node (ref "U3") (pin "8") (pinfunction "RG_8") (pintype "passive"))
    )
    (net (code "43") (name "Net-(U3-RG_2)") (class "Default")
      (node (ref "R18") (pin "1") (pinfunction "1_1") (pintype "passive"))
      (node (ref "U3") (pin "1") (pinfunction "RG_2_1") (pintype "passive"))
    )
    (net (code "44") (name "Net-(U4-RG)") (class "Default")
      (node (ref "R19") (pin "2") (pinfunction "2_2") (pintype "passive"))
      (node (ref "R19") (pin "3") (pinfunction "3_3") (pintype "passive"))
      (node (ref "U4") (pin "8") (pinfunction "RG_8") (pintype "passive"))
    )
    (net (code "45") (name "Net-(U4-RG_2)") (class "Default")
      (node (ref "R19") (pin "1") (pinfunction "1_1") (pintype "passive"))
      (node (ref "U4") (pin "1") (pinfunction "RG_2_1") (pintype "passive"))
    )
    (net (code "46") (name "Net-(U5-RG)") (class "Default")
      (node (ref "R20") (pin "2") (pinfunction "2_2") (pintype "passive"))
      (node (ref "R20") (pin "3") (pinfunction "3_3") (pintype "passive"))
      (node (ref "U5") (pin "8") (pinfunction "RG_8") (pintype "passive"))
    )
    (net (code "47") (name "Net-(U5-RG_2)") (class "Default")
      (node (ref "R20") (pin "1") (pinfunction "1_1") (pintype "passive"))
      (node (ref "U5") (pin "1") (pinfunction "RG_2_1") (pintype "passive"))
    )
    (net (code "48") (name "Net-(U6-RG)") (class "Default")
      (node (ref "R21") (pin "2") (pinfunction "2_2") (pintype "passive"))
      (node (ref "R21") (pin "3") (pinfunction "3_3") (pintype "passive"))
      (node (ref "U6") (pin "8") (pinfunction "RG_8") (pintype "passive"))
    )
    (net (code "49") (name "Net-(U6-RG_2)") (class "Default")
      (node (ref "R21") (pin "1") (pinfunction "1_1") (pintype "passive"))
      (node (ref "U6") (pin "1") (pinfunction "RG_2_1") (pintype "passive"))
    )
    (net (code "50") (name "Net-(U7-RG)") (class "Default")
      (node (ref "R22") (pin "2") (pinfunction "2_2") (pintype "passive"))
      (node (ref "R22") (pin "3") (pinfunction "3_3") (pintype "passive"))
      (node (ref "U7") (pin "8") (pinfunction "RG_8") (pintype "passive"))
    )
    (net (code "51") (name "Net-(U7-RG_2)") (class "Default")
      (node (ref "R22") (pin "1") (pinfunction "1_1") (pintype "passive"))
      (node (ref "U7") (pin "1") (pinfunction "RG_2_1") (pintype "passive"))
    )
    (net (code "52") (name "Net-(U8-RG)") (class "Default")
      (node (ref "R23") (pin "2") (pinfunction "2_2") (pintype "passive"))
      (node (ref "R23") (pin "3") (pinfunction "3_3") (pintype "passive"))
      (node (ref "U8") (pin "8") (pinfunction "RG_8") (pintype "passive"))
    )
    (net (code "53") (name "Net-(U8-RG_2)") (class "Default")
      (node (ref "R23") (pin "1") (pinfunction "1_1") (pintype "passive"))
      (node (ref "U8") (pin "1") (pinfunction "RG_2_1") (pintype "passive"))
    )
    (net (code "54") (name "SIG1+") (class "Default")
      (node (ref "C1") (pin "2") (pinfunction "2_2") (pintype "passive"))
      (node (ref "C10") (pin "1") (pinfunction "1_1") (pintype "passive"))
      (node (ref "R2") (pin "1") (pinfunction "1_1") (pintype "passive"))
      (node (ref "U1") (pin "3") (pinfunction "+IN_3") (pintype "passive"))
    )
    (net (code "55") (name "SIG1-") (class "Default")
      (node (ref "C1") (pin "1") (pinfunction "1_1") (pintype "passive"))
      (node (ref "C9") (pin "1") (pinfunction "1_1") (pintype "passive"))
      (node (ref "R1") (pin "1") (pinfunction "1_1") (pintype "passive"))
      (node (ref "U1") (pin "2") (pinfunction "-IN_2") (pintype "passive"))
    )
    (net (code "56") (name "SIG2+") (class "Default")
      (node (ref "C12") (pin "1") (pinfunction "1_1") (pintype "passive"))
      (node (ref "C2") (pin "2") (pinfunction "2_2") (pintype "passive"))
      (node (ref "R4") (pin "1") (pinfunction "1_1") (pintype "passive"))
      (node (ref "U2") (pin "3") (pinfunction "+IN_3") (pintype "passive"))
    )
    (net (code "57") (name "SIG2-") (class "Default")
      (node (ref "C11") (pin "1") (pinfunction "1_1") (pintype "passive"))
      (node (ref "C2") (pin "1") (pinfunction "1_1") (pintype "passive"))
      (node (ref "R3") (pin "1") (pinfunction "1_1") (pintype "passive"))
      (node (ref "U2") (pin "2") (pinfunction "-IN_2") (pintype "passive"))
    )
    (net (code "58") (name "SIG3+") (class "Default")
      (node (ref "C14") (pin "1") (pinfunction "1_1") (pintype "passive"))
      (node (ref "C3") (pin "2") (pinfunction "2_2") (pintype "passive"))
      (node (ref "R6") (pin "1") (pinfunction "1_1") (pintype "passive"))
      (node (ref "U3") (pin "3") (pinfunction "+IN_3") (pintype "passive"))
    )
    (net (code "59") (name "SIG3-") (class "Default")
      (node (ref "C13") (pin "1") (pinfunction "1_1") (pintype "passive"))
      (node (ref "C3") (pin "1") (pinfunction "1_1") (pintype "passive"))
      (node (ref "R5") (pin "1") (pinfunction "1_1") (pintype "passive"))
      (node (ref "U3") (pin "2") (pinfunction "-IN_2") (pintype "passive"))
    )
    (net (code "60") (name "SIG4+") (class "Default")
      (node (ref "C16") (pin "1") (pinfunction "1_1") (pintype "passive"))
      (node (ref "C4") (pin "2") (pinfunction "2_2") (pintype "passive"))
      (node (ref "R8") (pin "1") (pinfunction "1_1") (pintype "passive"))
      (node (ref "U4") (pin "3") (pinfunction "+IN_3") (pintype "passive"))
    )
    (net (code "61") (name "SIG4-") (class "Default")
      (node (ref "C15") (pin "1") (pinfunction "1_1") (pintype "passive"))
      (node (ref "C4") (pin "1") (pinfunction "1_1") (pintype "passive"))
      (node (ref "R7") (pin "1") (pinfunction "1_1") (pintype "passive"))
      (node (ref "U4") (pin "2") (pinfunction "-IN_2") (pintype "passive"))
    )
    (net (code "62") (name "SIG5+") (class "Default")
      (node (ref "C18") (pin "1") (pinfunction "1_1") (pintype "passive"))
      (node (ref "C5") (pin "2") (pinfunction "2_2") (pintype "passive"))
      (node (ref "R10") (pin "1") (pinfunction "1_1") (pintype "passive"))
      (node (ref "U5") (pin "3") (pinfunction "+IN_3") (pintype "passive"))
    )
    (net (code "63") (name "SIG5-") (class "Default")
      (node (ref "C17") (pin "1") (pinfunction "1_1") (pintype "passive"))
      (node (ref "C5") (pin "1") (pinfunction "1_1") (pintype "passive"))
      (node (ref "R9") (pin "1") (pinfunction "1_1") (pintype "passive"))
      (node (ref "U5") (pin "2") (pinfunction "-IN_2") (pintype "passive"))
    )
    (net (code "64") (name "SIG6+") (class "Default")
      (node (ref "C20") (pin "1") (pinfunction "1_1") (pintype "passive"))
      (node (ref "C6") (pin "2") (pinfunction "2_2") (pintype "passive"))
      (node (ref "R12") (pin "1") (pinfunction "1_1") (pintype "passive"))
      (node (ref "U6") (pin "3") (pinfunction "+IN_3") (pintype "passive"))
    )
    (net (code "65") (name "SIG6-") (class "Default")
      (node (ref "C19") (pin "1") (pinfunction "1_1") (pintype "passive"))
      (node (ref "C6") (pin "1") (pinfunction "1_1") (pintype "passive"))
      (node (ref "R11") (pin "1") (pinfunction "1_1") (pintype "passive"))
      (node (ref "U6") (pin "2") (pinfunction "-IN_2") (pintype "passive"))
    )
    (net (code "66") (name "SIG7+") (class "Default")
      (node (ref "C22") (pin "1") (pinfunction "1_1") (pintype "passive"))
      (node (ref "C7") (pin "2") (pinfunction "2_2") (pintype "passive"))
      (node (ref "R14") (pin "1") (pinfunction "1_1") (pintype "passive"))
      (node (ref "U7") (pin "3") (pinfunction "+IN_3") (pintype "passive"))
    )
    (net (code "67") (name "SIG7-") (class "Default")
      (node (ref "C21") (pin "1") (pinfunction "1_1") (pintype "passive"))
      (node (ref "C7") (pin "1") (pinfunction "1_1") (pintype "passive"))
      (node (ref "R13") (pin "1") (pinfunction "1_1") (pintype "passive"))
      (node (ref "U7") (pin "2") (pinfunction "-IN_2") (pintype "passive"))
    )
    (net (code "68") (name "SIG8+") (class "Default")
      (node (ref "C24") (pin "1") (pinfunction "1_1") (pintype "passive"))
      (node (ref "C8") (pin "2") (pinfunction "2_2") (pintype "passive"))
      (node (ref "R16") (pin "1") (pinfunction "1_1") (pintype "passive"))
      (node (ref "U8") (pin "3") (pinfunction "+IN_3") (pintype "passive"))
    )
    (net (code "69") (name "SIG8-") (class "Default")
      (node (ref "C23") (pin "1") (pinfunction "1_1") (pintype "passive"))
      (node (ref "C8") (pin "1") (pinfunction "1_1") (pintype "passive"))
      (node (ref "R15") (pin "1") (pinfunction "1_1") (pintype "passive"))
      (node (ref "U8") (pin "2") (pinfunction "-IN_2") (pintype "passive"))
    )
    (net (code "70") (name "unconnected-(IC1-+VOUT-Pad9)") (class "Default")
      (node (ref "IC1") (pin "9") (pinfunction "+VOUT_9") (pintype "bidirectional"))
    )
  )
)
